# TMC2660-test-with-grbl.net
KiCad netlist of a schematic drawn in EAGLE
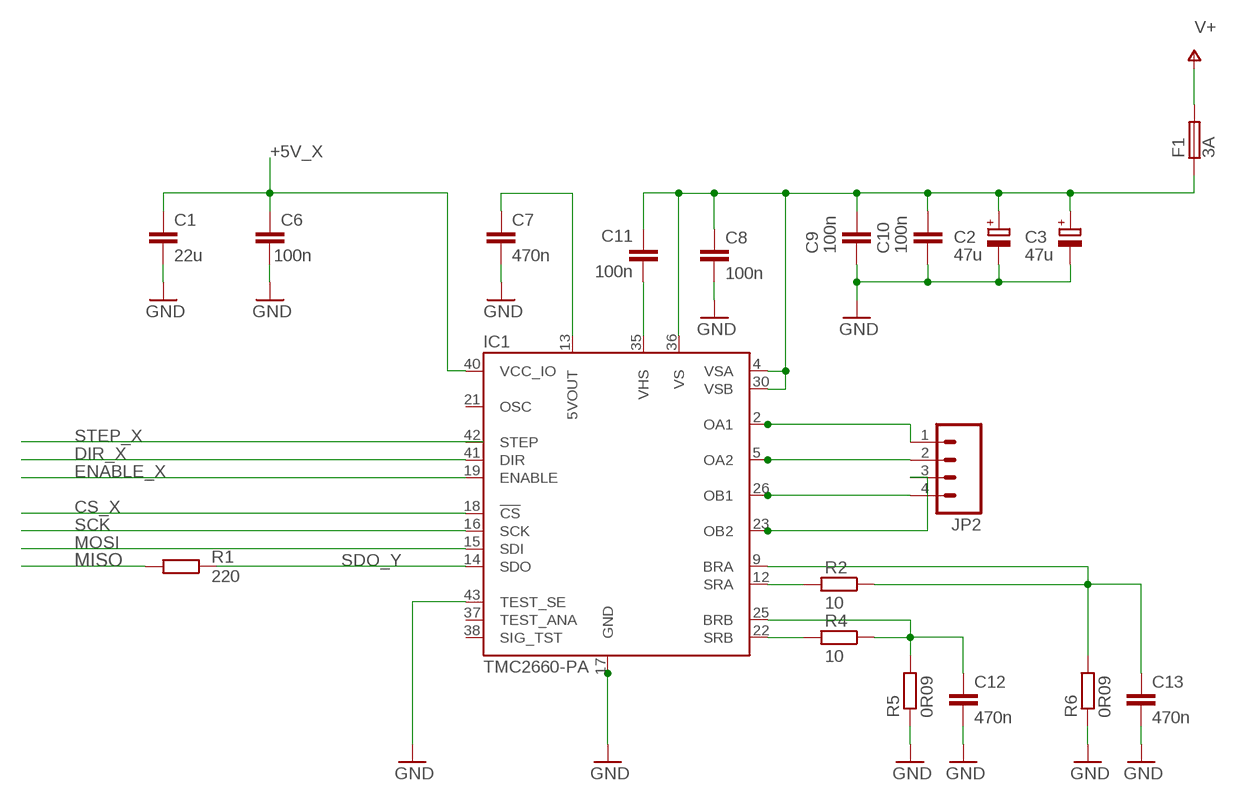
[diagram p0: schematic, sheet 1]
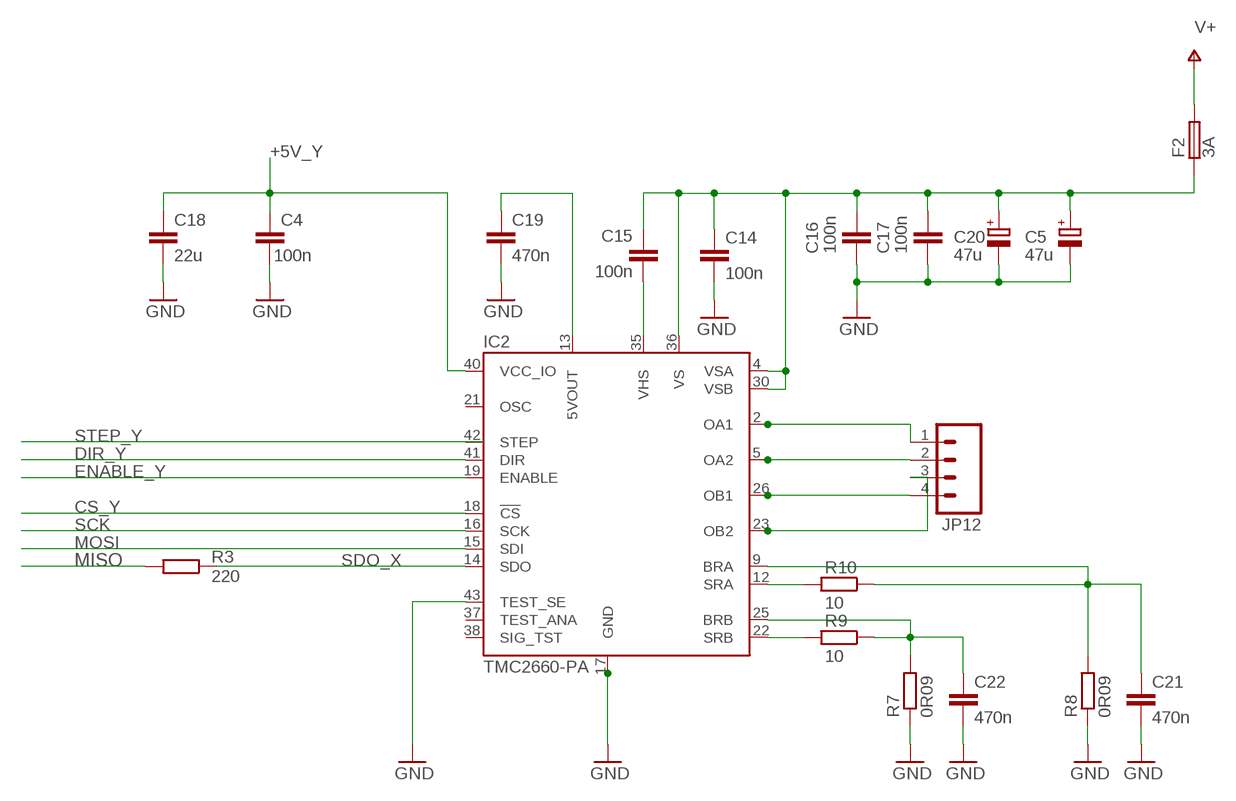
[diagram p1: schematic, sheet 2]
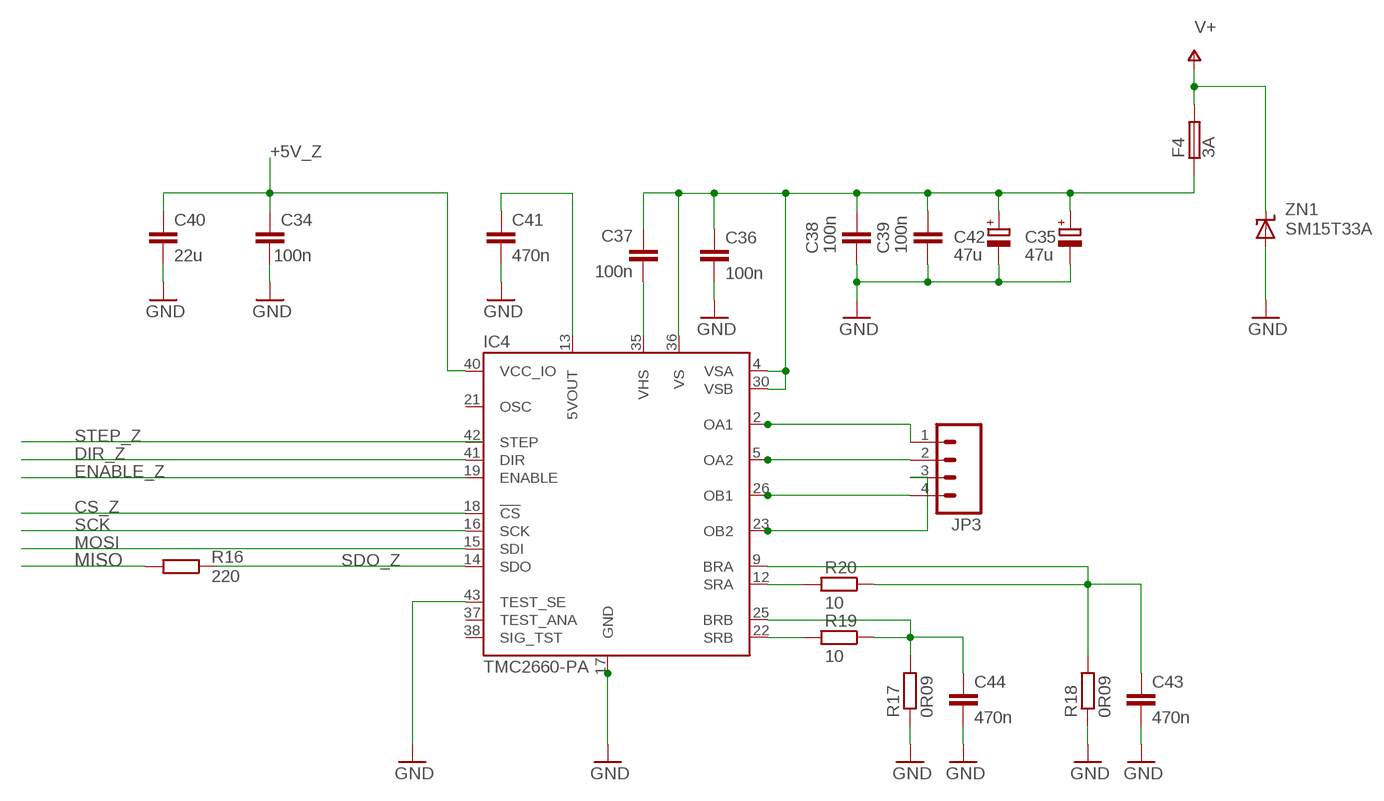
[diagram p2: schematic, sheet 3]
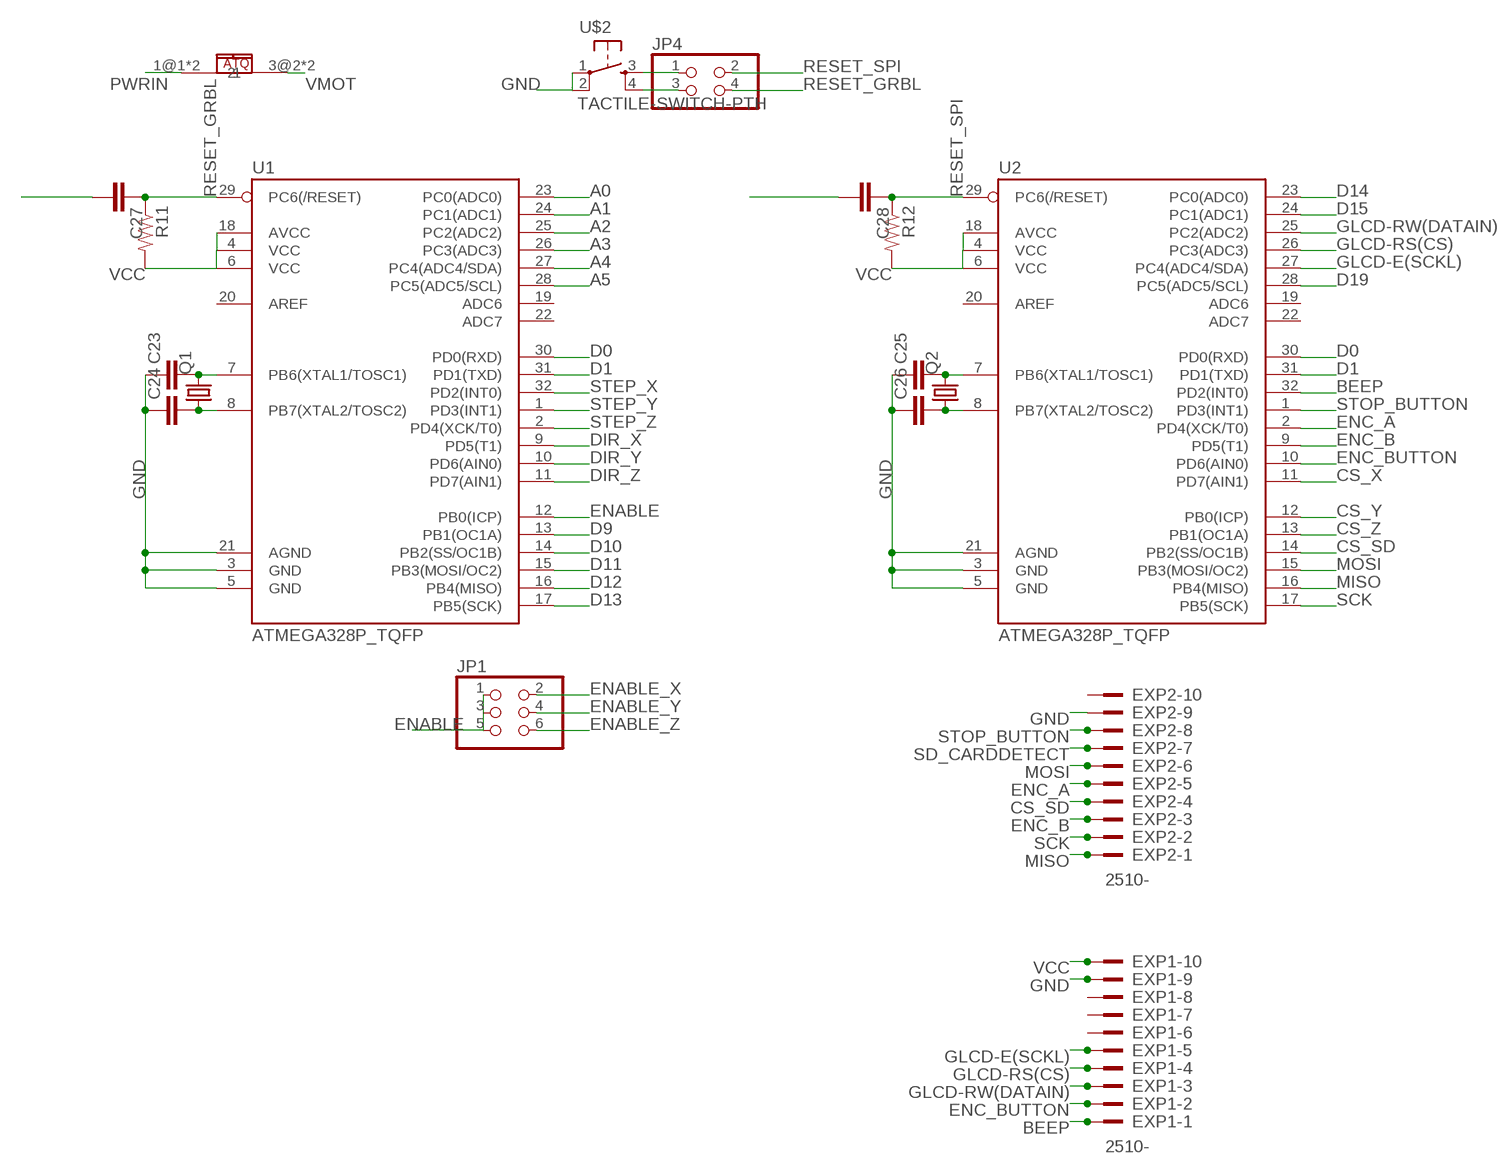
[diagram p3: schematic, sheet 4]

(export (version "E")
  (design (tool "Eeschema 10.0.6"))
  (components
    (comp (ref "C23")
      (value "CAP1206")
      (footprint "eagle-import:1206")
      (libsource (lib "eagle-import") (part "CAP1206"))
    )
    (comp (ref "C24")
      (value "CAP1206")
      (footprint "eagle-import:1206")
      (libsource (lib "eagle-import") (part "CAP1206"))
    )
    (comp (ref "C25")
      (value "CAP1206")
      (footprint "eagle-import:1206")
      (libsource (lib "eagle-import") (part "CAP1206"))
    )
    (comp (ref "C26")
      (value "CAP1206")
      (footprint "eagle-import:1206")
      (libsource (lib "eagle-import") (part "CAP1206"))
    )
    (comp (ref "C27")
      (value "CAP1206")
      (footprint "eagle-import:1206")
      (libsource (lib "eagle-import") (part "CAP1206"))
    )
    (comp (ref "C28")
      (value "CAP1206")
      (footprint "eagle-import:1206")
      (libsource (lib "eagle-import") (part "CAP1206"))
    )
    (comp (ref "EXP1")
      (value "2510-")
      (footprint "eagle-import:PAK100_2500-10")
      (fields (field (name "MF") "3M") (field (name "MPN") "2510-6002UB"))
      (libsource (lib "eagle-import") (part "2510-"))
    )
    (comp (ref "EXP2")
      (value "2510-")
      (footprint "eagle-import:PAK100_2500-10")
      (fields (field (name "MF") "3M") (field (name "MPN") "2510-6002UB"))
      (libsource (lib "eagle-import") (part "2510-"))
    )
    (comp (ref "JP1")
      (value "PINHD-2X3")
      (footprint "eagle-import:2X03")
      (libsource (lib "eagle-import") (part "PINHD-2X3"))
    )
    (comp (ref "JP4")
      (value "PINHD-2X2")
      (footprint "eagle-import:2X02")
      (libsource (lib "eagle-import") (part "PINHD-2X2"))
    )
    (comp (ref "Q1")
      (value "CRYSTALHC49UP")
      (footprint "eagle-import:HC49UP")
      (libsource (lib "eagle-import") (part "CRYSTALHC49UP"))
    )
    (comp (ref "Q2")
      (value "CRYSTALHC49UP")
      (footprint "eagle-import:HC49UP")
      (libsource (lib "eagle-import") (part "CRYSTALHC49UP"))
    )
    (comp (ref "R11")
      (value "RESISTOR1206")
      (footprint "eagle-import:1206")
      (libsource (lib "eagle-import") (part "RESISTOR1206"))
    )
    (comp (ref "R12")
      (value "RESISTOR1206")
      (footprint "eagle-import:1206")
      (libsource (lib "eagle-import") (part "RESISTOR1206"))
    )
    (comp (ref "U$2")
      (value "TACTILE-SWITCH-PTH")
      (footprint "eagle-import:TAC-SWITCH-PTH")
      (libsource (lib "eagle-import") (part "TACTILE-SWITCH-PTH"))
    )
    (comp (ref "U$6")
      (value "CQ-121")
      (footprint "eagle-import:CQ121")
      (libsource (lib "eagle-import") (part "CQ-121"))
    )
    (comp (ref "U1")
      (value "ATMEGA328P_TQFP")
      (footprint "eagle-import:TQFP32-08")
      (libsource (lib "eagle-import") (part "ATMEGA328P_TQFP"))
    )
    (comp (ref "U2")
      (value "ATMEGA328P_TQFP")
      (footprint "eagle-import:TQFP32-08")
      (libsource (lib "eagle-import") (part "ATMEGA328P_TQFP"))
    )
    (comp (ref "C4")
      (value "100n")
      (footprint "eagle-import:C1206K")
      (fields (field (name "MANUFACTURER") "Kemet") (field (name "VOLTAGE") "25V"))
      (libsource (lib "eagle-import") (part "C-EUC1206K"))
    )
    (comp (ref "C5")
      (value "47u")
      (footprint "eagle-import:E5-8,5")
      (fields (field (name "MANUFACTURER") "PANASONIC") (field (name "VOLTAGE") "50V"))
      (libsource (lib "eagle-import") (part "CPOL-EUE5-8.5"))
    )
    (comp (ref "C14")
      (value "100n")
      (footprint "eagle-import:C0603K")
      (fields (field (name "MANUFACTURER") "Kemet") (field (name "VOLTAGE") "50V"))
      (libsource (lib "eagle-import") (part "C-EUC0603K"))
    )
    (comp (ref "C15")
      (value "100n")
      (footprint "eagle-import:C0603K")
      (fields (field (name "MANUFACTURER") "Kemet") (field (name "VOLTAGE") "50V"))
      (libsource (lib "eagle-import") (part "C-EUC0603K"))
    )
    (comp (ref "C16")
      (value "100n")
      (footprint "eagle-import:C0603K")
      (fields (field (name "MANUFACTURER") "Kemet") (field (name "VOLTAGE") "50V"))
      (libsource (lib "eagle-import") (part "C-EUC0603K"))
    )
    (comp (ref "C17")
      (value "100n")
      (footprint "eagle-import:C0603K")
      (fields (field (name "MANUFACTURER") "Kemet") (field (name "VOLTAGE") "50V"))
      (libsource (lib "eagle-import") (part "C-EUC0603K"))
    )
    (comp (ref "C18")
      (value "22u")
      (footprint "eagle-import:C1206")
      (fields (field (name "MANUFACTURER") "Taiyo Yuden") (field (name "VOLTAGE") "6.3V"))
      (libsource (lib "eagle-import") (part "C-EUC1206"))
    )
    (comp (ref "C19")
      (value "470n")
      (footprint "eagle-import:0805-WIDE")
      (fields (field (name "MANUFACTURER") "Vishay") (field (name "VOLTAGE") "10V"))
      (libsource (lib "eagle-import") (part "C-0805W"))
    )
    (comp (ref "C20")
      (value "47u")
      (footprint "eagle-import:E5-8,5")
      (fields (field (name "MANUFACTURER") "PANASONIC") (field (name "VOLTAGE") "50V"))
      (libsource (lib "eagle-import") (part "CPOL-EUE5-8.5"))
    )
    (comp (ref "C21")
      (value "470n")
      (footprint "eagle-import:0805-WIDE")
      (fields (field (name "MANUFACTURER") "Vishay") (field (name "VOLTAGE") "10V"))
      (libsource (lib "eagle-import") (part "C-0805W"))
    )
    (comp (ref "C22")
      (value "470n")
      (footprint "eagle-import:0805-WIDE")
      (fields (field (name "MANUFACTURER") "Vishay") (field (name "VOLTAGE") "10V"))
      (libsource (lib "eagle-import") (part "C-0805W"))
    )
    (comp (ref "F2")
      (value "3A")
      (footprint "eagle-import:AF2")
      (fields
        (field (name "MANUFACTURER") "AEM")
        (field (name "MANUFACTURER_1") "Cooper Bussman")
        (field (name "PARTNR") "CB61F3A-TR2")
        (field (name "VOLTAGE") "125V")
      )
      (libsource (lib "eagle-import") (part "AF2-FUSE_AF"))
    )
    (comp (ref "IC2")
      (value "TMC2660-PA")
      (footprint "eagle-import:PQFP44")
      (fields (field (name "MANUFACTURER") "TRINAMIC"))
      (libsource (lib "eagle-import") (part "TMC2660-PA"))
    )
    (comp (ref "JP12")
      (value "M04SCREW")
      (footprint "eagle-import:SCREWTERMINAL-3.5MM-4")
      (libsource (lib "eagle-import") (part "M04SCREW"))
    )
    (comp (ref "R3")
      (value "220")
      (footprint "eagle-import:R0603")
      (fields (field (name "MANUFACTURER") "KOA Speer"))
      (libsource (lib "eagle-import") (part "R-EU_R0603"))
    )
    (comp (ref "R7")
      (value "0R09")
      (footprint "eagle-import:R2512")
      (fields (field (name "MANUFACTURER") "Panasonic") (field (name "POWER") "0.75W"))
      (libsource (lib "eagle-import") (part "R-EU_R2512"))
    )
    (comp (ref "R8")
      (value "0R09")
      (footprint "eagle-import:R2512")
      (fields (field (name "MANUFACTURER") "Panasonic") (field (name "POWER") "0.75W"))
      (libsource (lib "eagle-import") (part "R-EU_R2512"))
    )
    (comp (ref "R9")
      (value "10")
      (footprint "eagle-import:R0603")
      (fields (field (name "MANUFACTURER") "KOA Speer"))
      (libsource (lib "eagle-import") (part "R-EU_R0603"))
    )
    (comp (ref "R10")
      (value "10")
      (footprint "eagle-import:R0603")
      (fields (field (name "MANUFACTURER") "KOA Speer"))
      (libsource (lib "eagle-import") (part "R-EU_R0603"))
    )
    (comp (ref "C1")
      (value "22u")
      (footprint "eagle-import:C1206")
      (fields (field (name "MANUFACTURER") "Taiyo Yuden") (field (name "VOLTAGE") "6.3V"))
      (libsource (lib "eagle-import") (part "C-EUC1206"))
    )
    (comp (ref "C2")
      (value "47u")
      (footprint "eagle-import:E5-8,5")
      (fields (field (name "MANUFACTURER") "PANASONIC") (field (name "VOLTAGE") "50V"))
      (libsource (lib "eagle-import") (part "CPOL-EUE5-8.5"))
    )
    (comp (ref "C3")
      (value "47u")
      (footprint "eagle-import:E5-8,5")
      (fields (field (name "MANUFACTURER") "PANASONIC") (field (name "VOLTAGE") "50V"))
      (libsource (lib "eagle-import") (part "CPOL-EUE5-8.5"))
    )
    (comp (ref "C6")
      (value "100n")
      (footprint "eagle-import:C1206K")
      (fields (field (name "MANUFACTURER") "Kemet") (field (name "VOLTAGE") "25V"))
      (libsource (lib "eagle-import") (part "C-EUC1206K"))
    )
    (comp (ref "C7")
      (value "470n")
      (footprint "eagle-import:0805-WIDE")
      (fields (field (name "MANUFACTURER") "Vishay") (field (name "VOLTAGE") "10V"))
      (libsource (lib "eagle-import") (part "C-0805W"))
    )
    (comp (ref "C8")
      (value "100n")
      (footprint "eagle-import:C0603K")
      (fields (field (name "MANUFACTURER") "Kemet") (field (name "VOLTAGE") "50V"))
      (libsource (lib "eagle-import") (part "C-EUC0603K"))
    )
    (comp (ref "C9")
      (value "100n")
      (footprint "eagle-import:C0603K")
      (fields (field (name "MANUFACTURER") "Kemet") (field (name "VOLTAGE") "50V"))
      (libsource (lib "eagle-import") (part "C-EUC0603K"))
    )
    (comp (ref "C10")
      (value "100n")
      (footprint "eagle-import:C0603K")
      (fields (field (name "MANUFACTURER") "Kemet") (field (name "VOLTAGE") "50V"))
      (libsource (lib "eagle-import") (part "C-EUC0603K"))
    )
    (comp (ref "C11")
      (value "100n")
      (footprint "eagle-import:C0603K")
      (fields (field (name "MANUFACTURER") "Kemet") (field (name "VOLTAGE") "50V"))
      (libsource (lib "eagle-import") (part "C-EUC0603K"))
    )
    (comp (ref "C12")
      (value "470n")
      (footprint "eagle-import:0805-WIDE")
      (fields (field (name "MANUFACTURER") "Vishay") (field (name "VOLTAGE") "10V"))
      (libsource (lib "eagle-import") (part "C-0805W"))
    )
    (comp (ref "C13")
      (value "470n")
      (footprint "eagle-import:0805-WIDE")
      (fields (field (name "MANUFACTURER") "Vishay") (field (name "VOLTAGE") "10V"))
      (libsource (lib "eagle-import") (part "C-0805W"))
    )
    (comp (ref "F1")
      (value "3A")
      (footprint "eagle-import:AF2")
      (fields
        (field (name "MANUFACTURER") "AEM")
        (field (name "MANUFACTURER_1") "Cooper Bussman")
        (field (name "PARTNR") "CB61F3A-TR2")
        (field (name "VOLTAGE") "125V")
      )
      (libsource (lib "eagle-import") (part "AF2-FUSE_AF"))
    )
    (comp (ref "IC1")
      (value "TMC2660-PA")
      (footprint "eagle-import:PQFP44")
      (fields (field (name "MANUFACTURER") "TRINAMIC"))
      (libsource (lib "eagle-import") (part "TMC2660-PA"))
    )
    (comp (ref "JP2")
      (value "M04SCREW")
      (footprint "eagle-import:SCREWTERMINAL-3.5MM-4")
      (libsource (lib "eagle-import") (part "M04SCREW"))
    )
    (comp (ref "R1")
      (value "220")
      (footprint "eagle-import:R0603")
      (fields (field (name "MANUFACTURER") "KOA Speer"))
      (libsource (lib "eagle-import") (part "R-EU_R0603"))
    )
    (comp (ref "R2")
      (value "10")
      (footprint "eagle-import:R0603")
      (fields (field (name "MANUFACTURER") "KOA Speer"))
      (libsource (lib "eagle-import") (part "R-EU_R0603"))
    )
    (comp (ref "R4")
      (value "10")
      (footprint "eagle-import:R0603")
      (fields (field (name "MANUFACTURER") "KOA Speer"))
      (libsource (lib "eagle-import") (part "R-EU_R0603"))
    )
    (comp (ref "R5")
      (value "0R09")
      (footprint "eagle-import:R2512")
      (fields (field (name "MANUFACTURER") "Panasonic") (field (name "POWER") "0.75W"))
      (libsource (lib "eagle-import") (part "R-EU_R2512"))
    )
    (comp (ref "R6")
      (value "0R09")
      (footprint "eagle-import:R2512")
      (fields (field (name "MANUFACTURER") "Panasonic") (field (name "POWER") "0.75W"))
      (libsource (lib "eagle-import") (part "R-EU_R2512"))
    )
    (comp (ref "C34")
      (value "100n")
      (footprint "eagle-import:C1206K")
      (fields (field (name "MANUFACTURER") "Kemet") (field (name "VOLTAGE") "25V"))
      (libsource (lib "eagle-import") (part "C-EUC1206K"))
    )
    (comp (ref "C35")
      (value "47u")
      (footprint "eagle-import:E5-8,5")
      (fields (field (name "MANUFACTURER") "PANASONIC") (field (name "VOLTAGE") "50V"))
      (libsource (lib "eagle-import") (part "CPOL-EUE5-8.5"))
    )
    (comp (ref "C36")
      (value "100n")
      (footprint "eagle-import:C0603K")
      (fields (field (name "MANUFACTURER") "Kemet") (field (name "VOLTAGE") "50V"))
      (libsource (lib "eagle-import") (part "C-EUC0603K"))
    )
    (comp (ref "C37")
      (value "100n")
      (footprint "eagle-import:C0603K")
      (fields (field (name "MANUFACTURER") "Kemet") (field (name "VOLTAGE") "50V"))
      (libsource (lib "eagle-import") (part "C-EUC0603K"))
    )
    (comp (ref "C38")
      (value "100n")
      (footprint "eagle-import:C0603K")
      (fields (field (name "MANUFACTURER") "Kemet") (field (name "VOLTAGE") "50V"))
      (libsource (lib "eagle-import") (part "C-EUC0603K"))
    )
    (comp (ref "C39")
      (value "100n")
      (footprint "eagle-import:C0603K")
      (fields (field (name "MANUFACTURER") "Kemet") (field (name "VOLTAGE") "50V"))
      (libsource (lib "eagle-import") (part "C-EUC0603K"))
    )
    (comp (ref "C40")
      (value "22u")
      (footprint "eagle-import:C1206")
      (fields (field (name "MANUFACTURER") "Taiyo Yuden") (field (name "VOLTAGE") "6.3V"))
      (libsource (lib "eagle-import") (part "C-EUC1206"))
    )
    (comp (ref "C41")
      (value "470n")
      (footprint "eagle-import:0805-WIDE")
      (fields (field (name "MANUFACTURER") "Vishay") (field (name "VOLTAGE") "10V"))
      (libsource (lib "eagle-import") (part "C-0805W"))
    )
    (comp (ref "C42")
      (value "47u")
      (footprint "eagle-import:E5-8,5")
      (fields (field (name "MANUFACTURER") "PANASONIC") (field (name "VOLTAGE") "50V"))
      (libsource (lib "eagle-import") (part "CPOL-EUE5-8.5"))
    )
    (comp (ref "C43")
      (value "470n")
      (footprint "eagle-import:0805-WIDE")
      (fields (field (name "MANUFACTURER") "Vishay") (field (name "VOLTAGE") "10V"))
      (libsource (lib "eagle-import") (part "C-0805W"))
    )
    (comp (ref "C44")
      (value "470n")
      (footprint "eagle-import:0805-WIDE")
      (fields (field (name "MANUFACTURER") "Vishay") (field (name "VOLTAGE") "10V"))
      (libsource (lib "eagle-import") (part "C-0805W"))
    )
    (comp (ref "F4")
      (value "3A")
      (footprint "eagle-import:AF2")
      (fields
        (field (name "MANUFACTURER") "AEM")
        (field (name "MANUFACTURER_1") "Cooper Bussman")
        (field (name "PARTNR") "CB61F3A-TR2")
        (field (name "VOLTAGE") "125V")
      )
      (libsource (lib "eagle-import") (part "AF2-FUSE_AF"))
    )
    (comp (ref "IC4")
      (value "TMC2660-PA")
      (footprint "eagle-import:PQFP44")
      (fields (field (name "MANUFACTURER") "TRINAMIC"))
      (libsource (lib "eagle-import") (part "TMC2660-PA"))
    )
    (comp (ref "JP3")
      (value "M04SCREW")
      (footprint "eagle-import:SCREWTERMINAL-3.5MM-4")
      (libsource (lib "eagle-import") (part "M04SCREW"))
    )
    (comp (ref "R16")
      (value "220")
      (footprint "eagle-import:R0603")
      (fields (field (name "MANUFACTURER") "KOA Speer"))
      (libsource (lib "eagle-import") (part "R-EU_R0603"))
    )
    (comp (ref "R17")
      (value "0R09")
      (footprint "eagle-import:R2512")
      (fields (field (name "MANUFACTURER") "Panasonic") (field (name "POWER") "0.75W"))
      (libsource (lib "eagle-import") (part "R-EU_R2512"))
    )
    (comp (ref "R18")
      (value "0R09")
      (footprint "eagle-import:R2512")
      (fields (field (name "MANUFACTURER") "Panasonic") (field (name "POWER") "0.75W"))
      (libsource (lib "eagle-import") (part "R-EU_R2512"))
    )
    (comp (ref "R19")
      (value "10")
      (footprint "eagle-import:R0603")
      (fields (field (name "MANUFACTURER") "KOA Speer"))
      (libsource (lib "eagle-import") (part "R-EU_R0603"))
    )
    (comp (ref "R20")
      (value "10")
      (footprint "eagle-import:R0603")
      (fields (field (name "MANUFACTURER") "KOA Speer"))
      (libsource (lib "eagle-import") (part "R-EU_R0603"))
    )
    (comp (ref "ZN1")
      (value "SM15T33A")
      (footprint "eagle-import:SMC")
      (fields (field (name "MANUFACTURER") "ST"))
      (libsource (lib "eagle-import") (part "D-ZN_SMC"))
    )
  )
  (nets
    (net (code "1") (name "+5V_X") (class "Default")
      (node (ref "C1") (pin "1") (pinfunction "1_1") (pintype "passive"))
      (node (ref "C6") (pin "2") (pinfunction "2_2") (pintype "passive"))
      (node (ref "IC1") (pin "40") (pinfunction "VCC_IO_40") (pintype "bidirectional"))
    )
    (net (code "2") (name "+5V_Y") (class "Default")
      (node (ref "C18") (pin "1") (pinfunction "1_1") (pintype "passive"))
      (node (ref "C4") (pin "2") (pinfunction "2_2") (pintype "passive"))
      (node (ref "IC2") (pin "40") (pinfunction "VCC_IO_40") (pintype "bidirectional"))
    )
    (net (code "3") (name "+5V_Z") (class "Default")
      (node (ref "C34") (pin "2") (pinfunction "2_2") (pintype "passive"))
      (node (ref "C40") (pin "1") (pinfunction "1_1") (pintype "passive"))
      (node (ref "IC4") (pin "40") (pinfunction "VCC_IO_40") (pintype "bidirectional"))
    )
    (net (code "4") (name "A0") (class "Default")
      (node (ref "U1") (pin "23") (pinfunction "PC0(ADC0)_23") (pintype "bidirectional"))
    )
    (net (code "5") (name "A1") (class "Default")
      (node (ref "U1") (pin "24") (pinfunction "PC1(ADC1)_24") (pintype "bidirectional"))
    )
    (net (code "6") (name "A2") (class "Default")
      (node (ref "U1") (pin "25") (pinfunction "PC2(ADC2)_25") (pintype "bidirectional"))
    )
    (net (code "7") (name "A3") (class "Default")
      (node (ref "U1") (pin "26") (pinfunction "PC3(ADC3)_26") (pintype "bidirectional"))
    )
    (net (code "8") (name "A4") (class "Default")
      (node (ref "U1") (pin "27") (pinfunction "PC4(ADC4/SDA)_27") (pintype "bidirectional"))
    )
    (net (code "9") (name "A5") (class "Default")
      (node (ref "U1") (pin "28") (pinfunction "PC5(ADC5/SCL)_28") (pintype "bidirectional"))
    )
    (net (code "10") (name "BEEP") (class "Default")
      (node (ref "EXP1") (pin "1") (pinfunction "KL_1") (pintype "passive"))
      (node (ref "U2") (pin "32") (pinfunction "PD2(INT0)_32") (pintype "bidirectional"))
    )
    (net (code "11") (name "CS_SD") (class "Default")
      (node (ref "EXP2") (pin "4") (pinfunction "KL_4") (pintype "passive"))
      (node (ref "U2") (pin "14") (pinfunction "PB2(SS/OC1B)_14") (pintype "bidirectional"))
    )
    (net (code "12") (name "CS_X") (class "Default")
      (node (ref "IC1") (pin "18") (pinfunction "~{CS}_18") (pintype "bidirectional"))
      (node (ref "U2") (pin "11") (pinfunction "PD7(AIN1)_11") (pintype "bidirectional"))
    )
    (net (code "13") (name "CS_Y") (class "Default")
      (node (ref "IC2") (pin "18") (pinfunction "~{CS}_18") (pintype "bidirectional"))
      (node (ref "U2") (pin "12") (pinfunction "PB0(ICP)_12") (pintype "bidirectional"))
    )
    (net (code "14") (name "CS_Z") (class "Default")
      (node (ref "IC4") (pin "18") (pinfunction "~{CS}_18") (pintype "bidirectional"))
      (node (ref "U2") (pin "13") (pinfunction "PB1(OC1A)_13") (pintype "bidirectional"))
    )
    (net (code "15") (name "D0") (class "Default")
      (node (ref "U1") (pin "30") (pinfunction "PD0(RXD)_30") (pintype "bidirectional"))
      (node (ref "U2") (pin "30") (pinfunction "PD0(RXD)_30") (pintype "bidirectional"))
    )
    (net (code "16") (name "D1") (class "Default")
      (node (ref "U1") (pin "31") (pinfunction "PD1(TXD)_31") (pintype "bidirectional"))
      (node (ref "U2") (pin "31") (pinfunction "PD1(TXD)_31") (pintype "bidirectional"))
    )
    (net (code "17") (name "D9") (class "Default")
      (node (ref "U1") (pin "13") (pinfunction "PB1(OC1A)_13") (pintype "bidirectional"))
    )
    (net (code "18") (name "D10") (class "Default")
      (node (ref "U1") (pin "14") (pinfunction "PB2(SS/OC1B)_14") (pintype "bidirectional"))
    )
    (net (code "19") (name "D11") (class "Default")
      (node (ref "U1") (pin "15") (pinfunction "PB3(MOSI/OC2)_15") (pintype "bidirectional"))
    )
    (net (code "20") (name "D12") (class "Default")
      (node (ref "U1") (pin "16") (pinfunction "PB4(MISO)_16") (pintype "bidirectional"))
    )
    (net (code "21") (name "D13") (class "Default")
      (node (ref "U1") (pin "17") (pinfunction "PB5(SCK)_17") (pintype "bidirectional"))
    )
    (net (code "22") (name "D14") (class "Default")
      (node (ref "U2") (pin "23") (pinfunction "PC0(ADC0)_23") (pintype "bidirectional"))
    )
    (net (code "23") (name "D15") (class "Default")
      (node (ref "U2") (pin "24") (pinfunction "PC1(ADC1)_24") (pintype "bidirectional"))
    )
    (net (code "24") (name "D19") (class "Default")
      (node (ref "U2") (pin "28") (pinfunction "PC5(ADC5/SCL)_28") (pintype "bidirectional"))
    )
    (net (code "25") (name "DIR_X") (class "Default")
      (node (ref "IC1") (pin "41") (pinfunction "DIR_41") (pintype "bidirectional"))
      (node (ref "U1") (pin "9") (pinfunction "PD5(T1)_9") (pintype "bidirectional"))
    )
    (net (code "26") (name "DIR_Y") (class "Default")
      (node (ref "IC2") (pin "41") (pinfunction "DIR_41") (pintype "bidirectional"))
      (node (ref "U1") (pin "10") (pinfunction "PD6(AIN0)_10") (pintype "bidirectional"))
    )
    (net (code "27") (name "DIR_Z") (class "Default")
      (node (ref "IC4") (pin "41") (pinfunction "DIR_41") (pintype "bidirectional"))
      (node (ref "U1") (pin "11") (pinfunction "PD7(AIN1)_11") (pintype "bidirectional"))
    )
    (net (code "28") (name "ENABLE") (class "Default")
      (node (ref "JP1") (pin "1") (pinfunction "1_1") (pintype "passive"))
      (node (ref "JP1") (pin "3") (pinfunction "3_3") (pintype "passive"))
      (node (ref "JP1") (pin "5") (pinfunction "5_5") (pintype "passive"))
      (node (ref "U1") (pin "12") (pinfunction "PB0(ICP)_12") (pintype "bidirectional"))
    )
    (net (code "29") (name "ENABLE_X") (class "Default")
      (node (ref "IC1") (pin "19") (pinfunction "ENABLE_19") (pintype "bidirectional"))
      (node (ref "JP1") (pin "2") (pinfunction "2_2") (pintype "passive"))
    )
    (net (code "30") (name "ENABLE_Y") (class "Default")
      (node (ref "IC2") (pin "19") (pinfunction "ENABLE_19") (pintype "bidirectional"))
      (node (ref "JP1") (pin "4") (pinfunction "4_4") (pintype "passive"))
    )
    (net (code "31") (name "ENABLE_Z") (class "Default")
      (node (ref "IC4") (pin "19") (pinfunction "ENABLE_19") (pintype "bidirectional"))
      (node (ref "JP1") (pin "6") (pinfunction "6_6") (pintype "passive"))
    )
    (net (code "32") (name "ENC_A") (class "Default")
      (node (ref "EXP2") (pin "5") (pinfunction "KL_5") (pintype "passive"))
      (node (ref "U2") (pin "2") (pinfunction "PD4(XCK/T0)_2") (pintype "bidirectional"))
    )
    (net (code "33") (name "ENC_B") (class "Default")
      (node (ref "EXP2") (pin "3") (pinfunction "KL_3") (pintype "passive"))
      (node (ref "U2") (pin "9") (pinfunction "PD5(T1)_9") (pintype "bidirectional"))
    )
    (net (code "34") (name "ENC_BUTTON") (class "Default")
      (node (ref "EXP1") (pin "2") (pinfunction "KL_2") (pintype "passive"))
      (node (ref "U2") (pin "10") (pinfunction "PD6(AIN0)_10") (pintype "bidirectional"))
    )
    (net (code "35") (name "GLCD-E(SCKL)") (class "Default")
      (node (ref "EXP1") (pin "5") (pinfunction "KL_5") (pintype "passive"))
      (node (ref "U2") (pin "27") (pinfunction "PC4(ADC4/SDA)_27") (pintype "bidirectional"))
    )
    (net (code "36") (name "GLCD-RS(CS)") (class "Default")
      (node (ref "EXP1") (pin "4") (pinfunction "KL_4") (pintype "passive"))
      (node (ref "U2") (pin "26") (pinfunction "PC3(ADC3)_26") (pintype "bidirectional"))
    )
    (net (code "37") (name "GLCD-RW(DATAIN)") (class "Default")
      (node (ref "EXP1") (pin "3") (pinfunction "KL_3") (pintype "passive"))
      (node (ref "U2") (pin "25") (pinfunction "PC2(ADC2)_25") (pintype "bidirectional"))
    )
    (net (code "38") (name "GND") (class "Default")
      (node (ref "C1") (pin "2") (pinfunction "2_2") (pintype "passive"))
      (node (ref "C10") (pin "1") (pinfunction "1_1") (pintype "passive"))
      (node (ref "C12") (pin "2") (pinfunction "2_2") (pintype "passive"))
      (node (ref "C13") (pin "2") (pinfunction "2_2") (pintype "passive"))
      (node (ref "C14") (pin "2") (pinfunction "2_2") (pintype "passive"))
      (node (ref "C16") (pin "1") (pinfunction "1_1") (pintype "passive"))
      (node (ref "C17") (pin "1") (pinfunction "1_1") (pintype "passive"))
      (node (ref "C18") (pin "2") (pinfunction "2_2") (pintype "passive"))
      (node (ref "C19") (pin "2") (pinfunction "2_2") (pintype "passive"))
      (node (ref "C2") (pin "-") (pinfunction "-_-") (pintype "passive"))
      (node (ref "C20") (pin "-") (pinfunction "-_-") (pintype "passive"))
      (node (ref "C21") (pin "2") (pinfunction "2_2") (pintype "passive"))
      (node (ref "C22") (pin "2") (pinfunction "2_2") (pintype "passive"))
      (node (ref "C23") (pin "1") (pinfunction "1_1") (pintype "passive"))
      (node (ref "C24") (pin "1") (pinfunction "1_1") (pintype "passive"))
      (node (ref "C25") (pin "1") (pinfunction "1_1") (pintype "passive"))
      (node (ref "C26") (pin "1") (pinfunction "1_1") (pintype "passive"))
      (node (ref "C3") (pin "-") (pinfunction "-_-") (pintype "passive"))
      (node (ref "C34") (pin "1") (pinfunction "1_1") (pintype "passive"))
      (node (ref "C35") (pin "-") (pinfunction "-_-") (pintype "passive"))
      (node (ref "C36") (pin "2") (pinfunction "2_2") (pintype "passive"))
      (node (ref "C38") (pin "1") (pinfunction "1_1") (pintype "passive"))
      (node (ref "C39") (pin "1") (pinfunction "1_1") (pintype "passive"))
      (node (ref "C4") (pin "1") (pinfunction "1_1") (pintype "passive"))
      (node (ref "C40") (pin "2") (pinfunction "2_2") (pintype "passive"))
      (node (ref "C41") (pin "2") (pinfunction "2_2") (pintype "passive"))
      (node (ref "C42") (pin "-") (pinfunction "-_-") (pintype "passive"))
      (node (ref "C43") (pin "2") (pinfunction "2_2") (pintype "passive"))
      (node (ref "C44") (pin "2") (pinfunction "2_2") (pintype "passive"))
      (node (ref "C5") (pin "-") (pinfunction "-_-") (pintype "passive"))
      (node (ref "C6") (pin "1") (pinfunction "1_1") (pintype "passive"))
      (node (ref "C7") (pin "2") (pinfunction "2_2") (pintype "passive"))
      (node (ref "C8") (pin "2") (pinfunction "2_2") (pintype "passive"))
      (node (ref "C9") (pin "1") (pinfunction "1_1") (pintype "passive"))
      (node (ref "EXP1") (pin "9") (pinfunction "KL_9") (pintype "passive"))
      (node (ref "EXP2") (pin "9") (pinfunction "KL_9") (pintype "passive"))
      (node (ref "IC1") (pin "17") (pinfunction "GND_17") (pintype "bidirectional"))
      (node (ref "IC1") (pin "39") (pinfunction "GND1_39") (pintype "bidirectional"))
      (node (ref "IC1") (pin "43") (pinfunction "TEST_SE_43") (pintype "bidirectional"))
      (node (ref "IC1") (pin "44") (pinfunction "GND2_44") (pintype "bidirectional"))
      (node (ref "IC2") (pin "17") (pinfunction "GND_17") (pintype "bidirectional"))
      (node (ref "IC2") (pin "39") (pinfunction "GND1_39") (pintype "bidirectional"))
      (node (ref "IC2") (pin "43") (pinfunction "TEST_SE_43") (pintype "bidirectional"))
      (node (ref "IC2") (pin "44") (pinfunction "GND2_44") (pintype "bidirectional"))
      (node (ref "IC4") (pin "17") (pinfunction "GND_17") (pintype "bidirectional"))
      (node (ref "IC4") (pin "39") (pinfunction "GND1_39") (pintype "bidirectional"))
      (node (ref "IC4") (pin "43") (pinfunction "TEST_SE_43") (pintype "bidirectional"))
      (node (ref "IC4") (pin "44") (pinfunction "GND2_44") (pintype "bidirectional"))
      (node (ref "R17") (pin "1") (pinfunction "1_1") (pintype "passive"))
      (node (ref "R18") (pin "1") (pinfunction "1_1") (pintype "passive"))
      (node (ref "R5") (pin "1") (pinfunction "1_1") (pintype "passive"))
      (node (ref "R6") (pin "1") (pinfunction "1_1") (pintype "passive"))
      (node (ref "R7") (pin "1") (pinfunction "1_1") (pintype "passive"))
      (node (ref "R8") (pin "1") (pinfunction "1_1") (pintype "passive"))
      (node (ref "U$2") (pin "1") (pinfunction "1_1") (pintype "passive"))
      (node (ref "U$2") (pin "2") (pinfunction "2_2") (pintype "passive"))
      (node (ref "U1") (pin "21") (pinfunction "AGND_21") (pintype "bidirectional"))
      (node (ref "U1") (pin "3") (pinfunction "GND_3") (pintype "bidirectional"))
      (node (ref "U1") (pin "5") (pinfunction "GND_5") (pintype "bidirectional"))
      (node (ref "U2") (pin "21") (pinfunction "AGND_21") (pintype "bidirectional"))
      (node (ref "U2") (pin "3") (pinfunction "GND_3") (pintype "bidirectional"))
      (node (ref "U2") (pin "5") (pinfunction "GND_5") (pintype "bidirectional"))
      (node (ref "ZN1") (pin "P$2") (pinfunction "A_P$2") (pintype "passive"))
    )
    (net (code "39") (name "MISO") (class "Default")
      (node (ref "EXP2") (pin "1") (pinfunction "KL_1") (pintype "passive"))
      (node (ref "R1") (pin "2") (pinfunction "2_2") (pintype "passive"))
      (node (ref "R16") (pin "2") (pinfunction "2_2") (pintype "passive"))
      (node (ref "R3") (pin "2") (pinfunction "2_2") (pintype "passive"))
      (node (ref "U2") (pin "16") (pinfunction "PB4(MISO)_16") (pintype "bidirectional"))
    )
    (net (code "40") (name "MOSI") (class "Default")
      (node (ref "EXP2") (pin "6") (pinfunction "KL_6") (pintype "passive"))
      (node (ref "IC1") (pin "15") (pinfunction "SDI_15") (pintype "bidirectional"))
      (node (ref "IC2") (pin "15") (pinfunction "SDI_15") (pintype "bidirectional"))
      (node (ref "IC4") (pin "15") (pinfunction "SDI_15") (pintype "bidirectional"))
      (node (ref "U2") (pin "15") (pinfunction "PB3(MOSI/OC2)_15") (pintype "bidirectional"))
    )
    (net (code "41") (name "Net-(F1-1)") (class "Default")
      (node (ref "C10") (pin "2") (pinfunction "2_2") (pintype "passive"))
      (node (ref "C11") (pin "2") (pinfunction "2_2") (pintype "passive"))
      (node (ref "C2") (pin "+") (pinfunction "+_+") (pintype "passive"))
      (node (ref "C3") (pin "+") (pinfunction "+_+") (pintype "passive"))
      (node (ref "C8") (pin "1") (pinfunction "1_1") (pintype "passive"))
      (node (ref "C9") (pin "2") (pinfunction "2_2") (pintype "passive"))
      (node (ref "F1") (pin "P$1") (pinfunction "1_P$1") (pintype "passive"))
      (node (ref "IC1") (pin "30") (pinfunction "VSB_30") (pintype "bidirectional"))
      (node (ref "IC1") (pin "36") (pinfunction "VS_36") (pintype "bidirectional"))
      (node (ref "IC1") (pin "4") (pinfunction "VSA_4") (pintype "bidirectional"))
    )
    (net (code "42") (name "Net-(F2-1)") (class "Default")
      (node (ref "C14") (pin "1") (pinfunction "1_1") (pintype "passive"))
      (node (ref "C15") (pin "2") (pinfunction "2_2") (pintype "passive"))
      (node (ref "C16") (pin "2") (pinfunction "2_2") (pintype "passive"))
      (node (ref "C17") (pin "2") (pinfunction "2_2") (pintype "passive"))
      (node (ref "C20") (pin "+") (pinfunction "+_+") (pintype "passive"))
      (node (ref "C5") (pin "+") (pinfunction "+_+") (pintype "passive"))
      (node (ref "F2") (pin "P$1") (pinfunction "1_P$1") (pintype "passive"))
      (node (ref "IC2") (pin "30") (pinfunction "VSB_30") (pintype "bidirectional"))
      (node (ref "IC2") (pin "36") (pinfunction "VS_36") (pintype "bidirectional"))
      (node (ref "IC2") (pin "4") (pinfunction "VSA_4") (pintype "bidirectional"))
    )
    (net (code "43") (name "Net-(F4-1)") (class "Default")
      (node (ref "C35") (pin "+") (pinfunction "+_+") (pintype "passive"))
      (node (ref "C36") (pin "1") (pinfunction "1_1") (pintype "passive"))
      (node (ref "C37") (pin "2") (pinfunction "2_2") (pintype "passive"))
      (node (ref "C38") (pin "2") (pinfunction "2_2") (pintype "passive"))
      (node (ref "C39") (pin "2") (pinfunction "2_2") (pintype "passive"))
      (node (ref "C42") (pin "+") (pinfunction "+_+") (pintype "passive"))
      (node (ref "F4") (pin "P$1") (pinfunction "1_P$1") (pintype "passive"))
      (node (ref "IC4") (pin "30") (pinfunction "VSB_30") (pintype "bidirectional"))
      (node (ref "IC4") (pin "36") (pinfunction "VS_36") (pintype "bidirectional"))
      (node (ref "IC4") (pin "4") (pinfunction "VSA_4") (pintype "bidirectional"))
    )
    (net (code "44") (name "Net-(IC1-5VOUT)") (class "Default")
      (node (ref "C7") (pin "1") (pinfunction "1_1") (pintype "passive"))
      (node (ref "IC1") (pin "13") (pinfunction "5VOUT_13") (pintype "bidirectional"))
    )
    (net (code "45") (name "Net-(IC1-BRA)") (class "Default")
      (node (ref "C13") (pin "1") (pinfunction "1_1") (pintype "passive"))
      (node (ref "IC1") (pin "9") (pinfunction "BRA_9") (pintype "bidirectional"))
      (node (ref "R2") (pin "1") (pinfunction "1_1") (pintype "passive"))
      (node (ref "R6") (pin "2") (pinfunction "2_2") (pintype "passive"))
    )
    (net (code "46") (name "Net-(IC1-BRB)") (class "Default")
      (node (ref "C12") (pin "1") (pinfunction "1_1") (pintype "passive"))
      (node (ref "IC1") (pin "25") (pinfunction "BRB_25") (pintype "bidirectional"))
      (node (ref "R4") (pin "1") (pinfunction "1_1") (pintype "passive"))
      (node (ref "R5") (pin "2") (pinfunction "2_2") (pintype "passive"))
    )
    (net (code "47") (name "Net-(IC1-OA1)") (class "Default")
      (node (ref "IC1") (pin "2") (pinfunction "OA1_2") (pintype "bidirectional"))
      (node (ref "IC1") (pin "3") (pinfunction "OA1_1_3") (pintype "bidirectional"))
      (node (ref "IC1") (pin "7") (pinfunction "OA1_2_7") (pintype "bidirectional"))
      (node (ref "IC1") (pin "8") (pinfunction "OA1_3_8") (pintype "bidirectional"))
      (node (ref "JP2") (pin "1") (pinfunction "1_1") (pintype "passive"))
    )
    (net (code "48") (name "Net-(IC1-OA2)") (class "Default")
      (node (ref "IC1") (pin "10") (pinfunction "OA2_2_10") (pintype "bidirectional"))
      (node (ref "IC1") (pin "11") (pinfunction "OA2_3_11") (pintype "bidirectional"))
      (node (ref "IC1") (pin "5") (pinfunction "OA2_5") (pintype "bidirectional"))
      (node (ref "IC1") (pin "6") (pinfunction "OA2_1_6") (pintype "bidirectional"))
      (node (ref "JP2") (pin "2") (pinfunction "2_2") (pintype "passive"))
    )
    (net (code "49") (name "Net-(IC1-OB1)") (class "Default")
      (node (ref "IC1") (pin "26") (pinfunction "OB1_26") (pintype "bidirectional"))
      (node (ref "IC1") (pin "27") (pinfunction "OB1_1_27") (pintype "bidirectional"))
      (node (ref "IC1") (pin "31") (pinfunction "OB1_2_31") (pintype "bidirectional"))
      (node (ref "IC1") (pin "32") (pinfunction "OB1_3_32") (pintype "bidirectional"))
      (node (ref "JP2") (pin "4") (pinfunction "4_4") (pintype "passive"))
    )
    (net (code "50") (name "Net-(IC1-OB2)") (class "Default")
      (node (ref "IC1") (pin "23") (pinfunction "OB2_23") (pintype "bidirectional"))
      (node (ref "IC1") (pin "24") (pinfunction "OB2_1_24") (pintype "bidirectional"))
      (node (ref "IC1") (pin "28") (pinfunction "OB2_2_28") (pintype "bidirectional"))
      (node (ref "IC1") (pin "29") (pinfunction "OB2_3_29") (pintype "bidirectional"))
      (node (ref "JP2") (pin "3") (pinfunction "3_3") (pintype "passive"))
    )
    (net (code "51") (name "Net-(IC1-SRA)") (class "Default")
      (node (ref "IC1") (pin "12") (pinfunction "SRA_12") (pintype "bidirectional"))
      (node (ref "R2") (pin "2") (pinfunction "2_2") (pintype "passive"))
    )
    (net (code "52") (name "Net-(IC1-SRB)") (class "Default")
      (node (ref "IC1") (pin "22") (pinfunction "SRB_22") (pintype "bidirectional"))
      (node (ref "R4") (pin "2") (pinfunction "2_2") (pintype "passive"))
    )
    (net (code "53") (name "Net-(IC1-VHS)") (class "Default")
      (node (ref "C11") (pin "1") (pinfunction "1_1") (pintype "passive"))
      (node (ref "IC1") (pin "35") (pinfunction "VHS_35") (pintype "bidirectional"))
    )
    (net (code "54") (name "Net-(IC2-5VOUT)") (class "Default")
      (node (ref "C19") (pin "1") (pinfunction "1_1") (pintype "passive"))
      (node (ref "IC2") (pin "13") (pinfunction "5VOUT_13") (pintype "bidirectional"))
    )
    (net (code "55") (name "Net-(IC2-BRA)") (class "Default")
      (node (ref "C21") (pin "1") (pinfunction "1_1") (pintype "passive"))
      (node (ref "IC2") (pin "9") (pinfunction "BRA_9") (pintype "bidirectional"))
      (node (ref "R10") (pin "1") (pinfunction "1_1") (pintype "passive"))
      (node (ref "R8") (pin "2") (pinfunction "2_2") (pintype "passive"))
    )
    (net (code "56") (name "Net-(IC2-BRB)") (class "Default")
      (node (ref "C22") (pin "1") (pinfunction "1_1") (pintype "passive"))
      (node (ref "IC2") (pin "25") (pinfunction "BRB_25") (pintype "bidirectional"))
      (node (ref "R7") (pin "2") (pinfunction "2_2") (pintype "passive"))
      (node (ref "R9") (pin "1") (pinfunction "1_1") (pintype "passive"))
    )
    (net (code "57") (name "Net-(IC2-OA1)") (class "Default")
      (node (ref "IC2") (pin "2") (pinfunction "OA1_2") (pintype "bidirectional"))
      (node (ref "IC2") (pin "3") (pinfunction "OA1_1_3") (pintype "bidirectional"))
      (node (ref "IC2") (pin "7") (pinfunction "OA1_2_7") (pintype "bidirectional"))
      (node (ref "IC2") (pin "8") (pinfunction "OA1_3_8") (pintype "bidirectional"))
      (node (ref "JP12") (pin "1") (pinfunction "1_1") (pintype "passive"))
    )
    (net (code "58") (name "Net-(IC2-OA2)") (class "Default")
      (node (ref "IC2") (pin "10") (pinfunction "OA2_2_10") (pintype "bidirectional"))
      (node (ref "IC2") (pin "11") (pinfunction "OA2_3_11") (pintype "bidirectional"))
      (node (ref "IC2") (pin "5") (pinfunction "OA2_5") (pintype "bidirectional"))
      (node (ref "IC2") (pin "6") (pinfunction "OA2_1_6") (pintype "bidirectional"))
      (node (ref "JP12") (pin "2") (pinfunction "2_2") (pintype "passive"))
    )
    (net (code "59") (name "Net-(IC2-OB1)") (class "Default")
      (node (ref "IC2") (pin "26") (pinfunction "OB1_26") (pintype "bidirectional"))
      (node (ref "IC2") (pin "27") (pinfunction "OB1_1_27") (pintype "bidirectional"))
      (node (ref "IC2") (pin "31") (pinfunction "OB1_2_31") (pintype "bidirectional"))
      (node (ref "IC2") (pin "32") (pinfunction "OB1_3_32") (pintype "bidirectional"))
      (node (ref "JP12") (pin "4") (pinfunction "4_4") (pintype "passive"))
    )
    (net (code "60") (name "Net-(IC2-OB2)") (class "Default")
      (node (ref "IC2") (pin "23") (pinfunction "OB2_23") (pintype "bidirectional"))
      (node (ref "IC2") (pin "24") (pinfunction "OB2_1_24") (pintype "bidirectional"))
      (node (ref "IC2") (pin "28") (pinfunction "OB2_2_28") (pintype "bidirectional"))
      (node (ref "IC2") (pin "29") (pinfunction "OB2_3_29") (pintype "bidirectional"))
      (node (ref "JP12") (pin "3") (pinfunction "3_3") (pintype "passive"))
    )
    (net (code "61") (name "Net-(IC2-SRA)") (class "Default")
      (node (ref "IC2") (pin "12") (pinfunction "SRA_12") (pintype "bidirectional"))
      (node (ref "R10") (pin "2") (pinfunction "2_2") (pintype "passive"))
    )
    (net (code "62") (name "Net-(IC2-SRB)") (class "Default")
      (node (ref "IC2") (pin "22") (pinfunction "SRB_22") (pintype "bidirectional"))
      (node (ref "R9") (pin "2") (pinfunction "2_2") (pintype "passive"))
    )
    (net (code "63") (name "Net-(IC2-VHS)") (class "Default")
      (node (ref "C15") (pin "1") (pinfunction "1_1") (pintype "passive"))
      (node (ref "IC2") (pin "35") (pinfunction "VHS_35") (pintype "bidirectional"))
    )
    (net (code "64") (name "Net-(IC4-5VOUT)") (class "Default")
      (node (ref "C41") (pin "1") (pinfunction "1_1") (pintype "passive"))
      (node (ref "IC4") (pin "13") (pinfunction "5VOUT_13") (pintype "bidirectional"))
    )
    (net (code "65") (name "Net-(IC4-BRA)") (class "Default")
      (node (ref "C43") (pin "1") (pinfunction "1_1") (pintype "passive"))
      (node (ref "IC4") (pin "9") (pinfunction "BRA_9") (pintype "bidirectional"))
      (node (ref "R18") (pin "2") (pinfunction "2_2") (pintype "passive"))
      (node (ref "R20") (pin "1") (pinfunction "1_1") (pintype "passive"))
    )
    (net (code "66") (name "Net-(IC4-BRB)") (class "Default")
      (node (ref "C44") (pin "1") (pinfunction "1_1") (pintype "passive"))
      (node (ref "IC4") (pin "25") (pinfunction "BRB_25") (pintype "bidirectional"))
      (node (ref "R17") (pin "2") (pinfunction "2_2") (pintype "passive"))
      (node (ref "R19") (pin "1") (pinfunction "1_1") (pintype "passive"))
    )
    (net (code "67") (name "Net-(IC4-OA1)") (class "Default")
      (node (ref "IC4") (pin "2") (pinfunction "OA1_2") (pintype "bidirectional"))
      (node (ref "IC4") (pin "3") (pinfunction "OA1_1_3") (pintype "bidirectional"))
      (node (ref "IC4") (pin "7") (pinfunction "OA1_2_7") (pintype "bidirectional"))
      (node (ref "IC4") (pin "8") (pinfunction "OA1_3_8") (pintype "bidirectional"))
      (node (ref "JP3") (pin "1") (pinfunction "1_1") (pintype "passive"))
    )
    (net (code "68") (name "Net-(IC4-OA2)") (class "Default")
      (node (ref "IC4") (pin "10") (pinfunction "OA2_2_10") (pintype "bidirectional"))
      (node (ref "IC4") (pin "11") (pinfunction "OA2_3_11") (pintype "bidirectional"))
      (node (ref "IC4") (pin "5") (pinfunction "OA2_5") (pintype "bidirectional"))
      (node (ref "IC4") (pin "6") (pinfunction "OA2_1_6") (pintype "bidirectional"))
      (node (ref "JP3") (pin "2") (pinfunction "2_2") (pintype "passive"))
    )
    (net (code "69") (name "Net-(IC4-OB1)") (class "Default")
      (node (ref "IC4") (pin "26") (pinfunction "OB1_26") (pintype "bidirectional"))
      (node (ref "IC4") (pin "27") (pinfunction "OB1_1_27") (pintype "bidirectional"))
      (node (ref "IC4") (pin "31") (pinfunction "OB1_2_31") (pintype "bidirectional"))
      (node (ref "IC4") (pin "32") (pinfunction "OB1_3_32") (pintype "bidirectional"))
      (node (ref "JP3") (pin "4") (pinfunction "4_4") (pintype "passive"))
    )
    (net (code "70") (name "Net-(IC4-OB2)") (class "Default")
      (node (ref "IC4") (pin "23") (pinfunction "OB2_23") (pintype "bidirectional"))
      (node (ref "IC4") (pin "24") (pinfunction "OB2_1_24") (pintype "bidirectional"))
      (node (ref "IC4") (pin "28") (pinfunction "OB2_2_28") (pintype "bidirectional"))
      (node (ref "IC4") (pin "29") (pinfunction "OB2_3_29") (pintype "bidirectional"))
      (node (ref "JP3") (pin "3") (pinfunction "3_3") (pintype "passive"))
    )
    (net (code "71") (name "Net-(IC4-SRA)") (class "Default")
      (node (ref "IC4") (pin "12") (pinfunction "SRA_12") (pintype "bidirectional"))
      (node (ref "R20") (pin "2") (pinfunction "2_2") (pintype "passive"))
    )
    (net (code "72") (name "Net-(IC4-SRB)") (class "Default")
      (node (ref "IC4") (pin "22") (pinfunction "SRB_22") (pintype "bidirectional"))
      (node (ref "R19") (pin "2") (pinfunction "2_2") (pintype "passive"))
    )
    (net (code "73") (name "Net-(IC4-VHS)") (class "Default")
      (node (ref "C37") (pin "1") (pinfunction "1_1") (pintype "passive"))
      (node (ref "IC4") (pin "35") (pinfunction "VHS_35") (pintype "bidirectional"))
    )
    (net (code "74") (name "Net-(U1-PB6(XTAL1{slash}TOSC1))") (class "Default")
      (node (ref "C23") (pin "2") (pinfunction "2_2") (pintype "passive"))
      (node (ref "Q1") (pin "2") (pinfunction "2_2") (pintype "passive"))
      (node (ref "U1") (pin "7") (pinfunction "PB6(XTAL1/TOSC1)_7") (pintype "bidirectional"))
    )
    (net (code "75") (name "Net-(U1-PB7(XTAL2{slash}TOSC2))") (class "Default")
      (node (ref "C24") (pin "2") (pinfunction "2_2") (pintype "passive"))
      (node (ref "Q1") (pin "1") (pinfunction "1_1") (pintype "passive"))
      (node (ref "U1") (pin "8") (pinfunction "PB7(XTAL2/TOSC2)_8") (pintype "bidirectional"))
    )
    (net (code "76") (name "Net-(U2-PB6(XTAL1{slash}TOSC1))") (class "Default")
      (node (ref "C25") (pin "2") (pinfunction "2_2") (pintype "passive"))
      (node (ref "Q2") (pin "2") (pinfunction "2_2") (pintype "passive"))
      (node (ref "U2") (pin "7") (pinfunction "PB6(XTAL1/TOSC1)_7") (pintype "bidirectional"))
    )
    (net (code "77") (name "Net-(U2-PB7(XTAL2{slash}TOSC2))") (class "Default")
      (node (ref "C26") (pin "2") (pinfunction "2_2") (pintype "passive"))
      (node (ref "Q2") (pin "1") (pinfunction "1_1") (pintype "passive"))
      (node (ref "U2") (pin "8") (pinfunction "PB7(XTAL2/TOSC2)_8") (pintype "bidirectional"))
    )
    (net (code "78") (name "PWRIN") (class "Default")
      (node (ref "U$6") (pin "1@1") (pinfunction "1_1@1") (pintype "bidirectional"))
      (node (ref "U$6") (pin "2@1") (pinfunction "1_2@1") (pintype "bidirectional"))
    )
    (net (code "79") (name "RESET") (class "Default")
      (node (ref "JP4") (pin "1") (pinfunction "1_1") (pintype "passive"))
      (node (ref "JP4") (pin "3") (pinfunction "3_3") (pintype "passive"))
      (node (ref "U$2") (pin "3") (pinfunction "3_3") (pintype "passive"))
      (node (ref "U$2") (pin "4") (pinfunction "4_4") (pintype "passive"))
    )
    (net (code "80") (name "RESET_GRBL") (class "Default")
      (node (ref "C27") (pin "1") (pinfunction "1_1") (pintype "passive"))
      (node (ref "JP4") (pin "4") (pinfunction "4_4") (pintype "passive"))
      (node (ref "R11") (pin "1") (pinfunction "1_1") (pintype "passive"))
      (node (ref "U1") (pin "29") (pinfunction "PC6(/RESET)_29") (pintype "bidirectional"))
    )
    (net (code "81") (name "RESET_SPI") (class "Default")
      (node (ref "C28") (pin "1") (pinfunction "1_1") (pintype "passive"))
      (node (ref "JP4") (pin "2") (pinfunction "2_2") (pintype "passive"))
      (node (ref "R12") (pin "1") (pinfunction "1_1") (pintype "passive"))
      (node (ref "U2") (pin "29") (pinfunction "PC6(/RESET)_29") (pintype "bidirectional"))
    )
    (net (code "82") (name "SCK") (class "Default")
      (node (ref "EXP2") (pin "2") (pinfunction "KL_2") (pintype "passive"))
      (node (ref "IC1") (pin "16") (pinfunction "SCK_16") (pintype "bidirectional"))
      (node (ref "IC2") (pin "16") (pinfunction "SCK_16") (pintype "bidirectional"))
      (node (ref "IC4") (pin "16") (pinfunction "SCK_16") (pintype "bidirectional"))
      (node (ref "U2") (pin "17") (pinfunction "PB5(SCK)_17") (pintype "bidirectional"))
    )
    (net (code "83") (name "SDO_X") (class "Default")
      (node (ref "IC2") (pin "14") (pinfunction "SDO_14") (pintype "bidirectional"))
      (node (ref "R3") (pin "1") (pinfunction "1_1") (pintype "passive"))
    )
    (net (code "84") (name "SDO_Y") (class "Default")
      (node (ref "IC1") (pin "14") (pinfunction "SDO_14") (pintype "bidirectional"))
      (node (ref "R1") (pin "1") (pinfunction "1_1") (pintype "passive"))
    )
    (net (code "85") (name "SDO_Z") (class "Default")
      (node (ref "IC4") (pin "14") (pinfunction "SDO_14") (pintype "bidirectional"))
      (node (ref "R16") (pin "1") (pinfunction "1_1") (pintype "passive"))
    )
    (net (code "86") (name "SD_CARDDETECT") (class "Default")
      (node (ref "EXP2") (pin "7") (pinfunction "KL_7") (pintype "passive"))
    )
    (net (code "87") (name "STEP_X") (class "Default")
      (node (ref "IC1") (pin "42") (pinfunction "STEP_42") (pintype "bidirectional"))
      (node (ref "U1") (pin "32") (pinfunction "PD2(INT0)_32") (pintype "bidirectional"))
    )
    (net (code "88") (name "STEP_Y") (class "Default")
      (node (ref "IC2") (pin "42") (pinfunction "STEP_42") (pintype "bidirectional"))
      (node (ref "U1") (pin "1") (pinfunction "PD3(INT1)_1") (pintype "bidirectional"))
    )
    (net (code "89") (name "STEP_Z") (class "Default")
      (node (ref "IC4") (pin "42") (pinfunction "STEP_42") (pintype "bidirectional"))
      (node (ref "U1") (pin "2") (pinfunction "PD4(XCK/T0)_2") (pintype "bidirectional"))
    )
    (net (code "90") (name "STOP_BUTTON") (class "Default")
      (node (ref "EXP2") (pin "8") (pinfunction "KL_8") (pintype "passive"))
      (node (ref "U2") (pin "1") (pinfunction "PD3(INT1)_1") (pintype "bidirectional"))
    )
    (net (code "91") (name "V+") (class "Default")
      (node (ref "F1") (pin "P$2") (pinfunction "2_P$2") (pintype "passive"))
      (node (ref "F2") (pin "P$2") (pinfunction "2_P$2") (pintype "passive"))
      (node (ref "F4") (pin "P$2") (pinfunction "2_P$2") (pintype "passive"))
      (node (ref "ZN1") (pin "P$1") (pinfunction "C_P$1") (pintype "passive"))
    )
    (net (code "92") (name "VCC") (class "Default")
      (node (ref "EXP1") (pin "10") (pinfunction "KL_10") (pintype "passive"))
      (node (ref "R11") (pin "2") (pinfunction "2_2") (pintype "passive"))
      (node (ref "R12") (pin "2") (pinfunction "2_2") (pintype "passive"))
      (node (ref "U1") (pin "18") (pinfunction "AVCC_18") (pintype "bidirectional"))
      (node (ref "U1") (pin "4") (pinfunction "VCC_4") (pintype "bidirectional"))
      (node (ref "U1") (pin "6") (pinfunction "VCC_6") (pintype "bidirectional"))
      (node (ref "U2") (pin "18") (pinfunction "AVCC_18") (pintype "bidirectional"))
      (node (ref "U2") (pin "4") (pinfunction "VCC_4") (pintype "bidirectional"))
      (node (ref "U2") (pin "6") (pinfunction "VCC_6") (pintype "bidirectional"))
    )
    (net (code "93") (name "VMOT") (class "Default")
      (node (ref "U$6") (pin "3@2") (pinfunction "2_3@2") (pintype "bidirectional"))
      (node (ref "U$6") (pin "4@2") (pinfunction "2_4@2") (pintype "bidirectional"))
    )
    (net (code "94") (name "unconnected-(C27-Pad2)") (class "Default")
      (node (ref "C27") (pin "2") (pinfunction "2_2") (pintype "passive"))
    )
    (net (code "95") (name "unconnected-(C28-Pad2)") (class "Default")
      (node (ref "C28") (pin "2") (pinfunction "2_2") (pintype "passive"))
    )
    (net (code "96") (name "unconnected-(EXP1G-KL-Pad6)") (class "Default")
      (node (ref "EXP1") (pin "6") (pinfunction "KL_6") (pintype "passive"))
    )
    (net (code "97") (name "unconnected-(EXP1H-KL-Pad7)") (class "Default")
      (node (ref "EXP1") (pin "7") (pinfunction "KL_7") (pintype "passive"))
    )
    (net (code "98") (name "unconnected-(EXP1I-KL-Pad8)") (class "Default")
      (node (ref "EXP1") (pin "8") (pinfunction "KL_8") (pintype "passive"))
    )
    (net (code "99") (name "unconnected-(EXP2B-KL-Pad10)") (class "Default")
      (node (ref "EXP2") (pin "10") (pinfunction "KL_10") (pintype "passive"))
    )
    (net (code "100") (name "unconnected-(IC1-OSC-Pad21)") (class "Default")
      (node (ref "IC1") (pin "21") (pinfunction "OSC_21") (pintype "bidirectional"))
    )
    (net (code "101") (name "unconnected-(IC1-SIG_TST-Pad38)") (class "Default")
      (node (ref "IC1") (pin "38") (pinfunction "SIG_TST_38") (pintype "bidirectional"))
    )
    (net (code "102") (name "unconnected-(IC1-TEST_ANA-Pad37)") (class "Default")
      (node (ref "IC1") (pin "37") (pinfunction "TEST_ANA_37") (pintype "bidirectional"))
    )
    (net (code "103") (name "unconnected-(IC2-OSC-Pad21)") (class "Default")
      (node (ref "IC2") (pin "21") (pinfunction "OSC_21") (pintype "bidirectional"))
    )
    (net (code "104") (name "unconnected-(IC2-SIG_TST-Pad38)") (class "Default")
      (node (ref "IC2") (pin "38") (pinfunction "SIG_TST_38") (pintype "bidirectional"))
    )
    (net (code "105") (name "unconnected-(IC2-TEST_ANA-Pad37)") (class "Default")
      (node (ref "IC2") (pin "37") (pinfunction "TEST_ANA_37") (pintype "bidirectional"))
    )
    (net (code "106") (name "unconnected-(IC4-OSC-Pad21)") (class "Default")
      (node (ref "IC4") (pin "21") (pinfunction "OSC_21") (pintype "bidirectional"))
    )
    (net (code "107") (name "unconnected-(IC4-SIG_TST-Pad38)") (class "Default")
      (node (ref "IC4") (pin "38") (pinfunction "SIG_TST_38") (pintype "bidirectional"))
    )
    (net (code "108") (name "unconnected-(IC4-TEST_ANA-Pad37)") (class "Default")
      (node (ref "IC4") (pin "37") (pinfunction "TEST_ANA_37") (pintype "bidirectional"))
    )
    (net (code "109") (name "unconnected-(U1-ADC6-Pad19)") (class "Default")
      (node (ref "U1") (pin "19") (pinfunction "ADC6_19") (pintype "bidirectional"))
    )
    (net (code "110") (name "unconnected-(U1-ADC7-Pad22)") (class "Default")
      (node (ref "U1") (pin "22") (pinfunction "ADC7_22") (pintype "bidirectional"))
    )
    (net (code "111") (name "unconnected-(U1-AREF-Pad20)") (class "Default")
      (node (ref "U1") (pin "20") (pinfunction "AREF_20") (pintype "bidirectional"))
    )
    (net (code "112") (name "unconnected-(U2-ADC6-Pad19)") (class "Default")
      (node (ref "U2") (pin "19") (pinfunction "ADC6_19") (pintype "bidirectional"))
    )
    (net (code "113") (name "unconnected-(U2-ADC7-Pad22)") (class "Default")
      (node (ref "U2") (pin "22") (pinfunction "ADC7_22") (pintype "bidirectional"))
    )
    (net (code "114") (name "unconnected-(U2-AREF-Pad20)") (class "Default")
      (node (ref "U2") (pin "20") (pinfunction "AREF_20") (pintype "bidirectional"))
    )
  )
)
